# AltiumDesigner_-_Sheet_2.net
KiCad netlist of a schematic drawn in Altium Designer
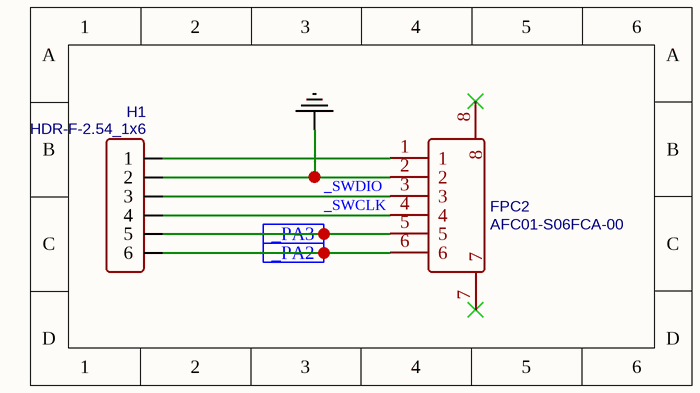
[diagram p0: AltiumDesigner - Sheet_2.schdoc]

(export (version "E")
  (design (tool "Eeschema 10.0.6"))
  (components
    (comp (ref "FPC2")
      (value "AFC01-S06FCA-00")
      (fields (field (name "BOM_SUPPLIER PART") "C262655") (field (name "CONTRIBUTOR") "LCSC"))
      (libsource (lib "altium-import") (part "root_0_AFC01-S06FCA-00_"))
    )
    (comp (ref "H1")
      (value "HDR-F-2.54_1x6")
      (fields (field (name "BOM_SUPPLIER PART") "C40877") (field (name "CONTRIBUTOR") "LCEDA_Lib"))
      (libsource (lib "altium-import") (part "root_0_HDR-F-2.54_1x6_"))
    )
  )
  (nets
    (net (code "1") (name "/_PA2") (class "Default")
      (node (ref "FPC2") (pin "6") (pinfunction "6_6") (pintype "passive"))
      (node (ref "H1") (pin "6") (pinfunction "6_6") (pintype "passive"))
    )
    (net (code "2") (name "/_PA3") (class "Default")
      (node (ref "FPC2") (pin "5") (pinfunction "5_5") (pintype "passive"))
      (node (ref "H1") (pin "5") (pinfunction "5_5") (pintype "passive"))
    )
    (net (code "3") (name "/_SWCLK") (class "Default")
      (node (ref "FPC2") (pin "4") (pinfunction "4_4") (pintype "passive"))
      (node (ref "H1") (pin "4") (pinfunction "4_4") (pintype "passive"))
    )
    (net (code "4") (name "/_SWDIO") (class "Default")
      (node (ref "FPC2") (pin "3") (pinfunction "3_3") (pintype "passive"))
      (node (ref "H1") (pin "3") (pinfunction "3_3") (pintype "passive"))
    )
    (net (code "5") (name "Net-(FPC2-Pad1)") (class "Default")
      (node (ref "FPC2") (pin "1") (pinfunction "1_1") (pintype "passive"))
      (node (ref "H1") (pin "1") (pinfunction "1_1") (pintype "passive"))
    )
    (net (code "6") (name "_GND") (class "Default")
      (node (ref "FPC2") (pin "2") (pinfunction "2_2") (pintype "passive"))
      (node (ref "H1") (pin "2") (pinfunction "2_2") (pintype "passive"))
    )
    (net (code "7") (name "unconnected-(FPC2-Pad7)") (class "Default")
      (node (ref "FPC2") (pin "7") (pinfunction "7_7") (pintype "passive+no_connect"))
    )
    (net (code "8") (name "unconnected-(FPC2-Pad8)") (class "Default")
      (node (ref "FPC2") (pin "8") (pinfunction "8_8") (pintype "passive+no_connect"))
    )
  )
)
